# SOC-Bootstrap.net
KiCad netlist of a schematic drawn in Altium Designer
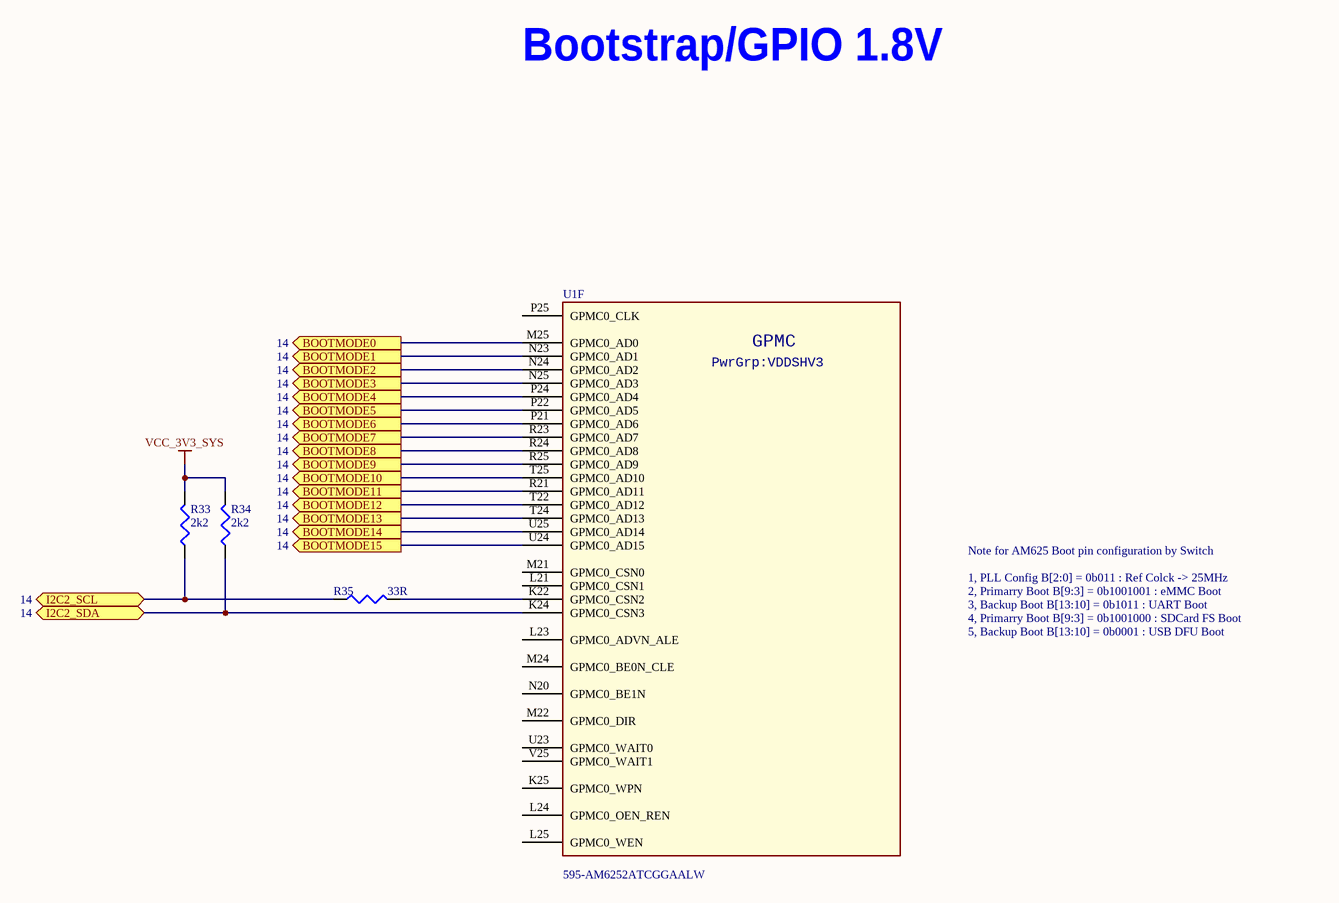
[diagram p0: SOC-Bootstrap.SchDoc]

(export (version "E")
  (design (tool "Eeschema 10.0.6"))
  (components
    (comp (ref "R33")
      (value "2k2")
      (footprint "R0402")
      (description "RES 2.20K OHM 1/16W 1% 0402 SMD")
      (fields
        (field (name "MANUFACTURER") "Yageo")
        (field (name "MANUFACTURER PART NUMBER") "RC0402FR-072K2L")
      )
      (libsource (lib "Schlib AM625") (part "RC0402FR-072K2L"))
    )
    (comp (ref "R34")
      (value "2k2")
      (footprint "R0402")
      (description "RES 2.20K OHM 1/16W 1% 0402 SMD")
      (fields
        (field (name "MANUFACTURER") "Yageo")
        (field (name "MANUFACTURER PART NUMBER") "RC0402FR-072K2L")
      )
      (libsource (lib "Schlib AM625") (part "RC0402FR-072K2L"))
    )
    (comp (ref "R35")
      (value "33R")
      (footprint "R0201")
      (description "RES 33 OHM 1% 1/20W 0201")
      (fields
        (field (name "MANUFACTURER") "Yageo")
        (field (name "MANUFACTURER PART NUMBER") "RC0201FR-0733RL")
      )
      (libsource (lib "Schlib AM625") (part "RC0201FR-0733RL"))
    )
    (comp (ref "U1")
      (value "AM62-EVM_BGA425")
      (footprint "BGA425C50P25X25_1300X1300X89")
      (description "ARM® Cortex®-A53 Microprocessor IC Sitara™ 2 Core, 64-Bit 1.4GHz 425-FCCSP (13x13)")
      (fields
        (field (name "MANUFACTURER") "Texas Instruments")
        (field (name "MANUFACTURER PART NUMBER") "AM6252ATCGGAALW")
        (field (name "SUPPLIER PART NUMBER 1") "595-AM6252ATCGGAALW")
      )
      (libsource (lib "Schlib AM625") (part "AM62-EVM_BGA425"))
    )
  )
  (nets
    (net (code "1") (name "/BOOTMODE0") (class "Default")
      (node (ref "U1") (pin "M25") (pinfunction "GPMC0_AD0_M25") (pintype "passive"))
    )
    (net (code "2") (name "/BOOTMODE1") (class "Default")
      (node (ref "U1") (pin "N23") (pinfunction "GPMC0_AD1_N23") (pintype "passive"))
    )
    (net (code "3") (name "/BOOTMODE2") (class "Default")
      (node (ref "U1") (pin "N24") (pinfunction "GPMC0_AD2_N24") (pintype "passive"))
    )
    (net (code "4") (name "/BOOTMODE3") (class "Default")
      (node (ref "U1") (pin "N25") (pinfunction "GPMC0_AD3_N25") (pintype "passive"))
    )
    (net (code "5") (name "/BOOTMODE4") (class "Default")
      (node (ref "U1") (pin "P24") (pinfunction "GPMC0_AD4_P24") (pintype "passive"))
    )
    (net (code "6") (name "/BOOTMODE5") (class "Default")
      (node (ref "U1") (pin "P22") (pinfunction "GPMC0_AD5_P22") (pintype "passive"))
    )
    (net (code "7") (name "/BOOTMODE6") (class "Default")
      (node (ref "U1") (pin "P21") (pinfunction "GPMC0_AD6_P21") (pintype "passive"))
    )
    (net (code "8") (name "/BOOTMODE7") (class "Default")
      (node (ref "U1") (pin "R23") (pinfunction "GPMC0_AD7_R23") (pintype "passive"))
    )
    (net (code "9") (name "/BOOTMODE8") (class "Default")
      (node (ref "U1") (pin "R24") (pinfunction "GPMC0_AD8_R24") (pintype "passive"))
    )
    (net (code "10") (name "/BOOTMODE9") (class "Default")
      (node (ref "U1") (pin "R25") (pinfunction "GPMC0_AD9_R25") (pintype "passive"))
    )
    (net (code "11") (name "/BOOTMODE10") (class "Default")
      (node (ref "U1") (pin "T25") (pinfunction "GPMC0_AD10_T25") (pintype "passive"))
    )
    (net (code "12") (name "/BOOTMODE11") (class "Default")
      (node (ref "U1") (pin "R21") (pinfunction "GPMC0_AD11_R21") (pintype "passive"))
    )
    (net (code "13") (name "/BOOTMODE12") (class "Default")
      (node (ref "U1") (pin "T22") (pinfunction "GPMC0_AD12_T22") (pintype "passive"))
    )
    (net (code "14") (name "/BOOTMODE13") (class "Default")
      (node (ref "U1") (pin "T24") (pinfunction "GPMC0_AD13_T24") (pintype "passive"))
    )
    (net (code "15") (name "/BOOTMODE14") (class "Default")
      (node (ref "U1") (pin "U25") (pinfunction "GPMC0_AD14_U25") (pintype "passive"))
    )
    (net (code "16") (name "/BOOTMODE15") (class "Default")
      (node (ref "U1") (pin "U24") (pinfunction "GPMC0_AD15_U24") (pintype "passive"))
    )
    (net (code "17") (name "/I2C2_SCL") (class "Default")
      (node (ref "R33") (pin "1") (pinfunction "1_1") (pintype "passive"))
      (node (ref "R35") (pin "1") (pinfunction "1_1") (pintype "passive"))
    )
    (net (code "18") (name "/I2C2_SDA") (class "Default")
      (node (ref "R34") (pin "1") (pinfunction "1_1") (pintype "passive"))
      (node (ref "U1") (pin "K24") (pinfunction "GPMC0_CSN3_K24") (pintype "passive"))
    )
    (net (code "19") (name "Net-(U1F-GPMC0_CSN2)") (class "Default")
      (node (ref "R35") (pin "2") (pinfunction "2_2") (pintype "passive"))
      (node (ref "U1") (pin "K22") (pinfunction "GPMC0_CSN2_K22") (pintype "passive"))
    )
    (net (code "20") (name "VCC_3V3_SYS") (class "Default")
      (node (ref "R33") (pin "2") (pinfunction "2_2") (pintype "passive"))
      (node (ref "R34") (pin "2") (pinfunction "2_2") (pintype "passive"))
    )
    (net (code "21") (name "unconnected-(U1F-GPMC0_ADVN_ALE-PadL23)") (class "Default")
      (node (ref "U1") (pin "L23") (pinfunction "GPMC0_ADVN_ALE_L23") (pintype "passive"))
    )
    (net (code "22") (name "unconnected-(U1F-GPMC0_BE0N_CLE-PadM24)") (class "Default")
      (node (ref "U1") (pin "M24") (pinfunction "GPMC0_BE0N_CLE_M24") (pintype "passive"))
    )
    (net (code "23") (name "unconnected-(U1F-GPMC0_BE1N-PadN20)") (class "Default")
      (node (ref "U1") (pin "N20") (pinfunction "GPMC0_BE1N_N20") (pintype "passive"))
    )
    (net (code "24") (name "unconnected-(U1F-GPMC0_CLK-PadP25)") (class "Default")
      (node (ref "U1") (pin "P25") (pinfunction "GPMC0_CLK_P25") (pintype "passive"))
    )
    (net (code "25") (name "unconnected-(U1F-GPMC0_CSN0-PadM21)") (class "Default")
      (node (ref "U1") (pin "M21") (pinfunction "GPMC0_CSN0_M21") (pintype "passive"))
    )
    (net (code "26") (name "unconnected-(U1F-GPMC0_CSN1-PadL21)") (class "Default")
      (node (ref "U1") (pin "L21") (pinfunction "GPMC0_CSN1_L21") (pintype "passive"))
    )
    (net (code "27") (name "unconnected-(U1F-GPMC0_DIR-PadM22)") (class "Default")
      (node (ref "U1") (pin "M22") (pinfunction "GPMC0_DIR_M22") (pintype "passive"))
    )
    (net (code "28") (name "unconnected-(U1F-GPMC0_OEN_REN-PadL24)") (class "Default")
      (node (ref "U1") (pin "L24") (pinfunction "GPMC0_OEN_REN_L24") (pintype "passive"))
    )
    (net (code "29") (name "unconnected-(U1F-GPMC0_WAIT0-PadU23)") (class "Default")
      (node (ref "U1") (pin "U23") (pinfunction "GPMC0_WAIT0_U23") (pintype "passive"))
    )
    (net (code "30") (name "unconnected-(U1F-GPMC0_WAIT1-PadV25)") (class "Default")
      (node (ref "U1") (pin "V25") (pinfunction "GPMC0_WAIT1_V25") (pintype "passive"))
    )
    (net (code "31") (name "unconnected-(U1F-GPMC0_WEN-PadL25)") (class "Default")
      (node (ref "U1") (pin "L25") (pinfunction "GPMC0_WEN_L25") (pintype "passive"))
    )
    (net (code "32") (name "unconnected-(U1F-GPMC0_WPN-PadK25)") (class "Default")
      (node (ref "U1") (pin "K25") (pinfunction "GPMC0_WPN_K25") (pintype "passive"))
    )
  )
)
